# x-Diodes_on_Back_Side.net
KiCad netlist of a schematic drawn in Altium Designer
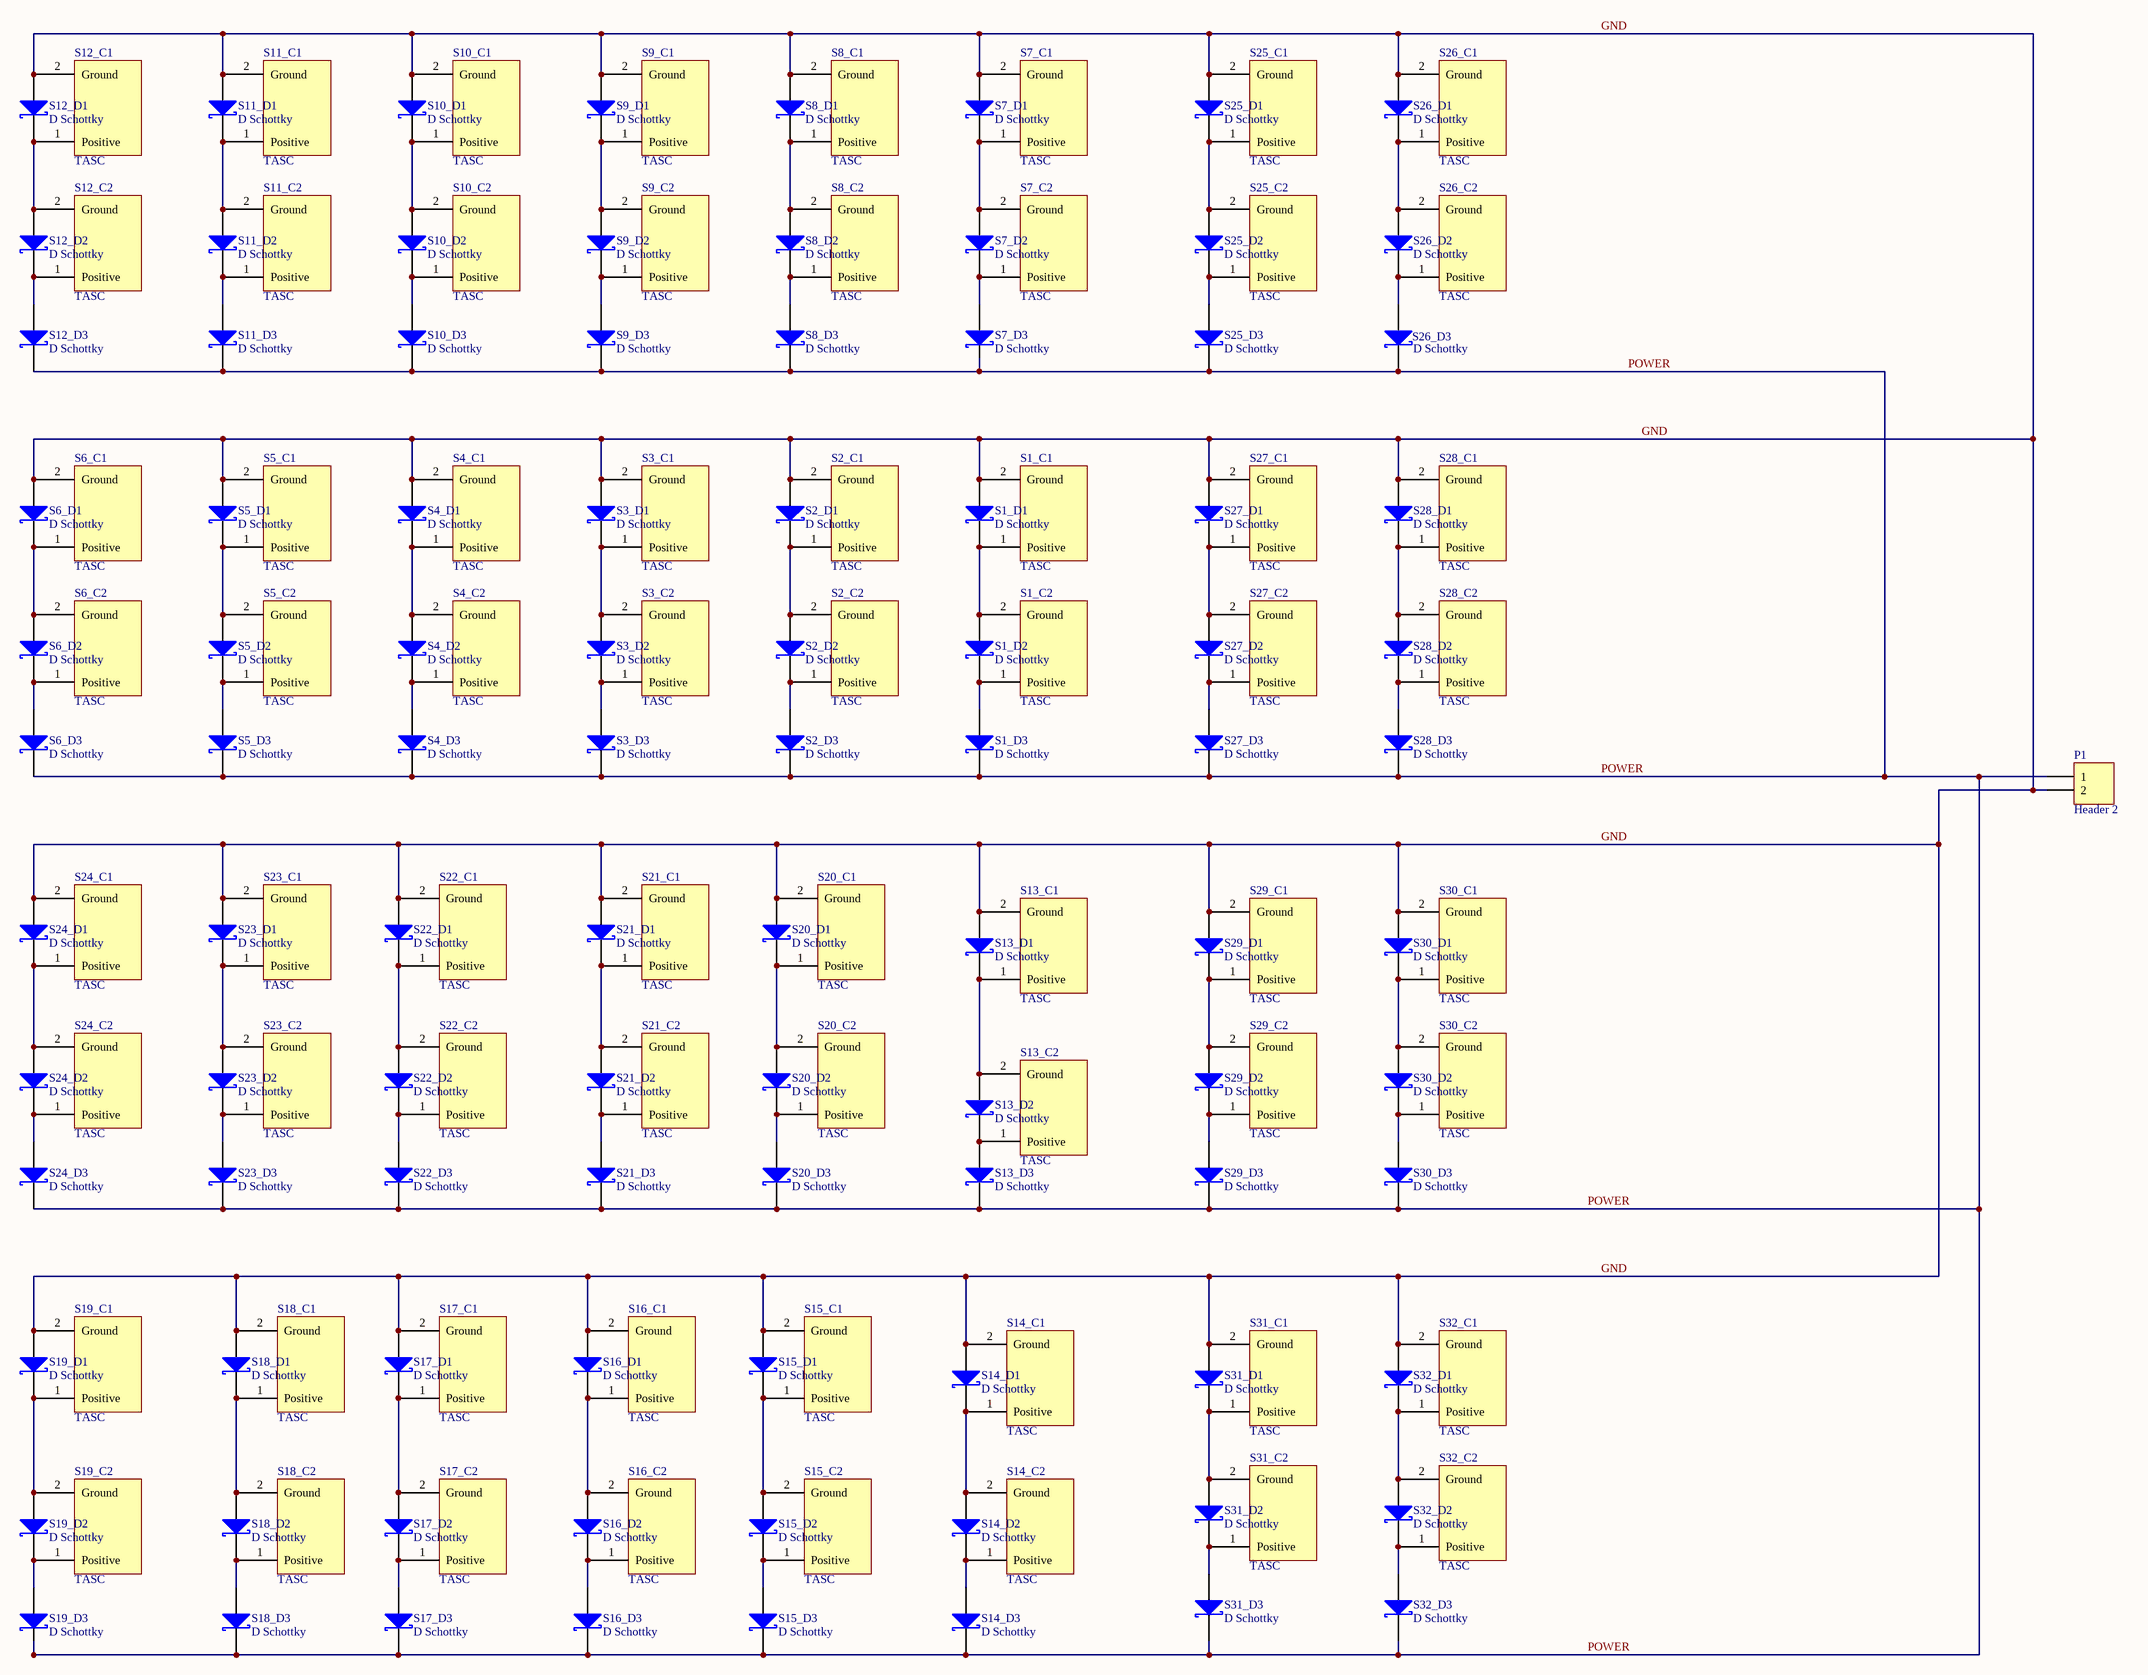
[diagram p0: x-Diodes on Back Side.SchDoc]

(export (version "E")
  (design (tool "Eeschema 10.0.6"))
  (components
    (comp (ref "P1")
      (value "Header 2")
      (footprint "HDR1X2")
      (description "Header, 2-Pin")
      (fields (field (name "PUBLISHER") "Altium Limited"))
      (libsource (lib "Miscellaneous Connectors") (part "Header 2"))
    )
    (comp (ref "S1_C1")
      (value "TASC")
      (footprint "PCBComponent_1")
      (description "TASC Solar Cell")
      (libsource (lib "SolarPanel1") (part "TASC"))
    )
    (comp (ref "S1_C2")
      (value "TASC")
      (footprint "PCBComponent_1")
      (description "TASC Solar Cell")
      (libsource (lib "SolarPanel1") (part "TASC"))
    )
    (comp (ref "S1_D1")
      (value "D Schottky")
      (footprint "SMB")
      (description "Schottky Diode")
      (fields (field (name "PUBLISHER") "Altium Limited"))
      (libsource (lib "Miscellaneous Devices") (part "D Schottky"))
    )
    (comp (ref "S1_D2")
      (value "D Schottky")
      (footprint "SMB")
      (description "Schottky Diode")
      (fields (field (name "PUBLISHER") "Altium Limited"))
      (libsource (lib "Miscellaneous Devices") (part "D Schottky"))
    )
    (comp (ref "S1_D3")
      (value "D Schottky")
      (footprint "SMB")
      (description "Schottky Diode")
      (fields (field (name "PUBLISHER") "Altium Limited"))
      (libsource (lib "Miscellaneous Devices") (part "D Schottky"))
    )
    (comp (ref "S2_C1")
      (value "TASC")
      (footprint "PCBComponent_1")
      (description "TASC Solar Cell")
      (libsource (lib "SolarPanel1") (part "TASC"))
    )
    (comp (ref "S2_C2")
      (value "TASC")
      (footprint "PCBComponent_1")
      (description "TASC Solar Cell")
      (libsource (lib "SolarPanel1") (part "TASC"))
    )
    (comp (ref "S2_D1")
      (value "D Schottky")
      (footprint "SMB")
      (description "Schottky Diode")
      (fields (field (name "PUBLISHER") "Altium Limited"))
      (libsource (lib "Miscellaneous Devices") (part "D Schottky"))
    )
    (comp (ref "S2_D2")
      (value "D Schottky")
      (footprint "SMB")
      (description "Schottky Diode")
      (fields (field (name "PUBLISHER") "Altium Limited"))
      (libsource (lib "Miscellaneous Devices") (part "D Schottky"))
    )
    (comp (ref "S2_D3")
      (value "D Schottky")
      (footprint "SMB")
      (description "Schottky Diode")
      (fields (field (name "PUBLISHER") "Altium Limited"))
      (libsource (lib "Miscellaneous Devices") (part "D Schottky"))
    )
    (comp (ref "S3_C1")
      (value "TASC")
      (footprint "PCBComponent_1")
      (description "TASC Solar Cell")
      (libsource (lib "SolarPanel1") (part "TASC"))
    )
    (comp (ref "S3_C2")
      (value "TASC")
      (footprint "PCBComponent_1")
      (description "TASC Solar Cell")
      (libsource (lib "SolarPanel1") (part "TASC"))
    )
    (comp (ref "S3_D1")
      (value "D Schottky")
      (footprint "SMB")
      (description "Schottky Diode")
      (fields (field (name "PUBLISHER") "Altium Limited"))
      (libsource (lib "Miscellaneous Devices") (part "D Schottky"))
    )
    (comp (ref "S3_D2")
      (value "D Schottky")
      (footprint "SMB")
      (description "Schottky Diode")
      (fields (field (name "PUBLISHER") "Altium Limited"))
      (libsource (lib "Miscellaneous Devices") (part "D Schottky"))
    )
    (comp (ref "S3_D3")
      (value "D Schottky")
      (footprint "SMB")
      (description "Schottky Diode")
      (fields (field (name "PUBLISHER") "Altium Limited"))
      (libsource (lib "Miscellaneous Devices") (part "D Schottky"))
    )
    (comp (ref "S4_C1")
      (value "TASC")
      (footprint "PCBComponent_1")
      (description "TASC Solar Cell")
      (libsource (lib "SolarPanel1") (part "TASC"))
    )
    (comp (ref "S4_C2")
      (value "TASC")
      (footprint "PCBComponent_1")
      (description "TASC Solar Cell")
      (libsource (lib "SolarPanel1") (part "TASC"))
    )
    (comp (ref "S4_D1")
      (value "D Schottky")
      (footprint "SMB")
      (description "Schottky Diode")
      (fields (field (name "PUBLISHER") "Altium Limited"))
      (libsource (lib "Miscellaneous Devices") (part "D Schottky"))
    )
    (comp (ref "S4_D2")
      (value "D Schottky")
      (footprint "SMB")
      (description "Schottky Diode")
      (fields (field (name "PUBLISHER") "Altium Limited"))
      (libsource (lib "Miscellaneous Devices") (part "D Schottky"))
    )
    (comp (ref "S4_D3")
      (value "D Schottky")
      (footprint "SMB")
      (description "Schottky Diode")
      (fields (field (name "PUBLISHER") "Altium Limited"))
      (libsource (lib "Miscellaneous Devices") (part "D Schottky"))
    )
    (comp (ref "S5_C1")
      (value "TASC")
      (footprint "PCBComponent_1")
      (description "TASC Solar Cell")
      (libsource (lib "SolarPanel1") (part "TASC"))
    )
    (comp (ref "S5_C2")
      (value "TASC")
      (footprint "PCBComponent_1")
      (description "TASC Solar Cell")
      (libsource (lib "SolarPanel1") (part "TASC"))
    )
    (comp (ref "S5_D1")
      (value "D Schottky")
      (footprint "SMB")
      (description "Schottky Diode")
      (fields (field (name "PUBLISHER") "Altium Limited"))
      (libsource (lib "Miscellaneous Devices") (part "D Schottky"))
    )
    (comp (ref "S5_D2")
      (value "D Schottky")
      (footprint "SMB")
      (description "Schottky Diode")
      (fields (field (name "PUBLISHER") "Altium Limited"))
      (libsource (lib "Miscellaneous Devices") (part "D Schottky"))
    )
    (comp (ref "S5_D3")
      (value "D Schottky")
      (footprint "SMB")
      (description "Schottky Diode")
      (fields (field (name "PUBLISHER") "Altium Limited"))
      (libsource (lib "Miscellaneous Devices") (part "D Schottky"))
    )
    (comp (ref "S6_C1")
      (value "TASC")
      (footprint "PCBComponent_1")
      (description "TASC Solar Cell")
      (libsource (lib "SolarPanel1") (part "TASC"))
    )
    (comp (ref "S6_C2")
      (value "TASC")
      (footprint "PCBComponent_1")
      (description "TASC Solar Cell")
      (libsource (lib "SolarPanel1") (part "TASC"))
    )
    (comp (ref "S6_D1")
      (value "D Schottky")
      (footprint "SMB")
      (description "Schottky Diode")
      (fields (field (name "PUBLISHER") "Altium Limited"))
      (libsource (lib "Miscellaneous Devices") (part "D Schottky"))
    )
    (comp (ref "S6_D2")
      (value "D Schottky")
      (footprint "SMB")
      (description "Schottky Diode")
      (fields (field (name "PUBLISHER") "Altium Limited"))
      (libsource (lib "Miscellaneous Devices") (part "D Schottky"))
    )
    (comp (ref "S6_D3")
      (value "D Schottky")
      (footprint "SMB")
      (description "Schottky Diode")
      (fields (field (name "PUBLISHER") "Altium Limited"))
      (libsource (lib "Miscellaneous Devices") (part "D Schottky"))
    )
    (comp (ref "S7_C1")
      (value "TASC")
      (footprint "PCBComponent_1")
      (description "TASC Solar Cell")
      (libsource (lib "SolarPanel1") (part "TASC"))
    )
    (comp (ref "S7_C2")
      (value "TASC")
      (footprint "PCBComponent_1")
      (description "TASC Solar Cell")
      (libsource (lib "SolarPanel1") (part "TASC"))
    )
    (comp (ref "S7_D1")
      (value "D Schottky")
      (footprint "SMB")
      (description "Schottky Diode")
      (fields (field (name "PUBLISHER") "Altium Limited"))
      (libsource (lib "Miscellaneous Devices") (part "D Schottky"))
    )
    (comp (ref "S7_D2")
      (value "D Schottky")
      (footprint "SMB")
      (description "Schottky Diode")
      (fields (field (name "PUBLISHER") "Altium Limited"))
      (libsource (lib "Miscellaneous Devices") (part "D Schottky"))
    )
    (comp (ref "S7_D3")
      (value "D Schottky")
      (footprint "SMB")
      (description "Schottky Diode")
      (fields (field (name "PUBLISHER") "Altium Limited"))
      (libsource (lib "Miscellaneous Devices") (part "D Schottky"))
    )
    (comp (ref "S8_C1")
      (value "TASC")
      (footprint "PCBComponent_1")
      (description "TASC Solar Cell")
      (libsource (lib "SolarPanel1") (part "TASC"))
    )
    (comp (ref "S8_C2")
      (value "TASC")
      (footprint "PCBComponent_1")
      (description "TASC Solar Cell")
      (libsource (lib "SolarPanel1") (part "TASC"))
    )
    (comp (ref "S8_D1")
      (value "D Schottky")
      (footprint "SMB")
      (description "Schottky Diode")
      (fields (field (name "PUBLISHER") "Altium Limited"))
      (libsource (lib "Miscellaneous Devices") (part "D Schottky"))
    )
    (comp (ref "S8_D2")
      (value "D Schottky")
      (footprint "SMB")
      (description "Schottky Diode")
      (fields (field (name "PUBLISHER") "Altium Limited"))
      (libsource (lib "Miscellaneous Devices") (part "D Schottky"))
    )
    (comp (ref "S8_D3")
      (value "D Schottky")
      (footprint "SMB")
      (description "Schottky Diode")
      (fields (field (name "PUBLISHER") "Altium Limited"))
      (libsource (lib "Miscellaneous Devices") (part "D Schottky"))
    )
    (comp (ref "S9_C1")
      (value "TASC")
      (footprint "PCBComponent_1")
      (description "TASC Solar Cell")
      (libsource (lib "SolarPanel1") (part "TASC"))
    )
    (comp (ref "S9_C2")
      (value "TASC")
      (footprint "PCBComponent_1")
      (description "TASC Solar Cell")
      (libsource (lib "SolarPanel1") (part "TASC"))
    )
    (comp (ref "S9_D1")
      (value "D Schottky")
      (footprint "SMB")
      (description "Schottky Diode")
      (fields (field (name "PUBLISHER") "Altium Limited"))
      (libsource (lib "Miscellaneous Devices") (part "D Schottky"))
    )
    (comp (ref "S9_D2")
      (value "D Schottky")
      (footprint "SMB")
      (description "Schottky Diode")
      (fields (field (name "PUBLISHER") "Altium Limited"))
      (libsource (lib "Miscellaneous Devices") (part "D Schottky"))
    )
    (comp (ref "S9_D3")
      (value "D Schottky")
      (footprint "SMB")
      (description "Schottky Diode")
      (fields (field (name "PUBLISHER") "Altium Limited"))
      (libsource (lib "Miscellaneous Devices") (part "D Schottky"))
    )
    (comp (ref "S10_C1")
      (value "TASC")
      (footprint "PCBComponent_1")
      (description "TASC Solar Cell")
      (libsource (lib "SolarPanel1") (part "TASC"))
    )
    (comp (ref "S10_C2")
      (value "TASC")
      (footprint "PCBComponent_1")
      (description "TASC Solar Cell")
      (libsource (lib "SolarPanel1") (part "TASC"))
    )
    (comp (ref "S10_D1")
      (value "D Schottky")
      (footprint "SMB")
      (description "Schottky Diode")
      (fields (field (name "PUBLISHER") "Altium Limited"))
      (libsource (lib "Miscellaneous Devices") (part "D Schottky"))
    )
    (comp (ref "S10_D2")
      (value "D Schottky")
      (footprint "SMB")
      (description "Schottky Diode")
      (fields (field (name "PUBLISHER") "Altium Limited"))
      (libsource (lib "Miscellaneous Devices") (part "D Schottky"))
    )
    (comp (ref "S10_D3")
      (value "D Schottky")
      (footprint "SMB")
      (description "Schottky Diode")
      (fields (field (name "PUBLISHER") "Altium Limited"))
      (libsource (lib "Miscellaneous Devices") (part "D Schottky"))
    )
    (comp (ref "S11_C1")
      (value "TASC")
      (footprint "PCBComponent_1")
      (description "TASC Solar Cell")
      (libsource (lib "SolarPanel1") (part "TASC"))
    )
    (comp (ref "S11_C2")
      (value "TASC")
      (footprint "PCBComponent_1")
      (description "TASC Solar Cell")
      (libsource (lib "SolarPanel1") (part "TASC"))
    )
    (comp (ref "S11_D1")
      (value "D Schottky")
      (footprint "SMB")
      (description "Schottky Diode")
      (fields (field (name "PUBLISHER") "Altium Limited"))
      (libsource (lib "Miscellaneous Devices") (part "D Schottky"))
    )
    (comp (ref "S11_D2")
      (value "D Schottky")
      (footprint "SMB")
      (description "Schottky Diode")
      (fields (field (name "PUBLISHER") "Altium Limited"))
      (libsource (lib "Miscellaneous Devices") (part "D Schottky"))
    )
    (comp (ref "S11_D3")
      (value "D Schottky")
      (footprint "SMB")
      (description "Schottky Diode")
      (fields (field (name "PUBLISHER") "Altium Limited"))
      (libsource (lib "Miscellaneous Devices") (part "D Schottky"))
    )
    (comp (ref "S12_C1")
      (value "TASC")
      (footprint "PCBComponent_1")
      (description "TASC Solar Cell")
      (libsource (lib "SolarPanel1") (part "TASC"))
    )
    (comp (ref "S12_C2")
      (value "TASC")
      (footprint "PCBComponent_1")
      (description "TASC Solar Cell")
      (libsource (lib "SolarPanel1") (part "TASC"))
    )
    (comp (ref "S12_D1")
      (value "D Schottky")
      (footprint "SMB")
      (description "Schottky Diode")
      (fields (field (name "PUBLISHER") "Altium Limited"))
      (libsource (lib "Miscellaneous Devices") (part "D Schottky"))
    )
    (comp (ref "S12_D2")
      (value "D Schottky")
      (footprint "SMB")
      (description "Schottky Diode")
      (fields (field (name "PUBLISHER") "Altium Limited"))
      (libsource (lib "Miscellaneous Devices") (part "D Schottky"))
    )
    (comp (ref "S12_D3")
      (value "D Schottky")
      (footprint "SMB")
      (description "Schottky Diode")
      (fields (field (name "PUBLISHER") "Altium Limited"))
      (libsource (lib "Miscellaneous Devices") (part "D Schottky"))
    )
    (comp (ref "S13_C1")
      (value "TASC")
      (footprint "PCBComponent_1")
      (description "TASC Solar Cell")
      (libsource (lib "SolarPanel1") (part "TASC"))
    )
    (comp (ref "S13_C2")
      (value "TASC")
      (footprint "PCBComponent_1")
      (description "TASC Solar Cell")
      (libsource (lib "SolarPanel1") (part "TASC"))
    )
    (comp (ref "S13_D1")
      (value "D Schottky")
      (footprint "SMB")
      (description "Schottky Diode")
      (fields (field (name "PUBLISHER") "Altium Limited"))
      (libsource (lib "Miscellaneous Devices") (part "D Schottky"))
    )
    (comp (ref "S13_D2")
      (value "D Schottky")
      (footprint "SMB")
      (description "Schottky Diode")
      (fields (field (name "PUBLISHER") "Altium Limited"))
      (libsource (lib "Miscellaneous Devices") (part "D Schottky"))
    )
    (comp (ref "S13_D3")
      (value "D Schottky")
      (footprint "SMB")
      (description "Schottky Diode")
      (fields (field (name "PUBLISHER") "Altium Limited"))
      (libsource (lib "Miscellaneous Devices") (part "D Schottky"))
    )
    (comp (ref "S14_C1")
      (value "TASC")
      (footprint "PCBComponent_1")
      (description "TASC Solar Cell")
      (libsource (lib "SolarPanel1") (part "TASC"))
    )
    (comp (ref "S14_C2")
      (value "TASC")
      (footprint "PCBComponent_1")
      (description "TASC Solar Cell")
      (libsource (lib "SolarPanel1") (part "TASC"))
    )
    (comp (ref "S14_D1")
      (value "D Schottky")
      (footprint "SMB")
      (description "Schottky Diode")
      (fields (field (name "PUBLISHER") "Altium Limited"))
      (libsource (lib "Miscellaneous Devices") (part "D Schottky"))
    )
    (comp (ref "S14_D2")
      (value "D Schottky")
      (footprint "SMB")
      (description "Schottky Diode")
      (fields (field (name "PUBLISHER") "Altium Limited"))
      (libsource (lib "Miscellaneous Devices") (part "D Schottky"))
    )
    (comp (ref "S14_D3")
      (value "D Schottky")
      (footprint "SMB")
      (description "Schottky Diode")
      (fields (field (name "PUBLISHER") "Altium Limited"))
      (libsource (lib "Miscellaneous Devices") (part "D Schottky"))
    )
    (comp (ref "S15_C1")
      (value "TASC")
      (footprint "PCBComponent_1")
      (description "TASC Solar Cell")
      (libsource (lib "SolarPanel1") (part "TASC"))
    )
    (comp (ref "S15_C2")
      (value "TASC")
      (footprint "PCBComponent_1")
      (description "TASC Solar Cell")
      (libsource (lib "SolarPanel1") (part "TASC"))
    )
    (comp (ref "S15_D1")
      (value "D Schottky")
      (footprint "SMB")
      (description "Schottky Diode")
      (fields (field (name "PUBLISHER") "Altium Limited"))
      (libsource (lib "Miscellaneous Devices") (part "D Schottky"))
    )
    (comp (ref "S15_D2")
      (value "D Schottky")
      (footprint "SMB")
      (description "Schottky Diode")
      (fields (field (name "PUBLISHER") "Altium Limited"))
      (libsource (lib "Miscellaneous Devices") (part "D Schottky"))
    )
    (comp (ref "S15_D3")
      (value "D Schottky")
      (footprint "SMB")
      (description "Schottky Diode")
      (fields (field (name "PUBLISHER") "Altium Limited"))
      (libsource (lib "Miscellaneous Devices") (part "D Schottky"))
    )
    (comp (ref "S16_C1")
      (value "TASC")
      (footprint "PCBComponent_1")
      (description "TASC Solar Cell")
      (libsource (lib "SolarPanel1") (part "TASC"))
    )
    (comp (ref "S16_C2")
      (value "TASC")
      (footprint "PCBComponent_1")
      (description "TASC Solar Cell")
      (libsource (lib "SolarPanel1") (part "TASC"))
    )
    (comp (ref "S16_D1")
      (value "D Schottky")
      (footprint "SMB")
      (description "Schottky Diode")
      (fields (field (name "PUBLISHER") "Altium Limited"))
      (libsource (lib "Miscellaneous Devices") (part "D Schottky"))
    )
    (comp (ref "S16_D2")
      (value "D Schottky")
      (footprint "SMB")
      (description "Schottky Diode")
      (fields (field (name "PUBLISHER") "Altium Limited"))
      (libsource (lib "Miscellaneous Devices") (part "D Schottky"))
    )
    (comp (ref "S16_D3")
      (value "D Schottky")
      (footprint "SMB")
      (description "Schottky Diode")
      (fields (field (name "PUBLISHER") "Altium Limited"))
      (libsource (lib "Miscellaneous Devices") (part "D Schottky"))
    )
    (comp (ref "S17_C1")
      (value "TASC")
      (footprint "PCBComponent_1")
      (description "TASC Solar Cell")
      (libsource (lib "SolarPanel1") (part "TASC"))
    )
    (comp (ref "S17_C2")
      (value "TASC")
      (footprint "PCBComponent_1")
      (description "TASC Solar Cell")
      (libsource (lib "SolarPanel1") (part "TASC"))
    )
    (comp (ref "S17_D1")
      (value "D Schottky")
      (footprint "SMB")
      (description "Schottky Diode")
      (fields (field (name "PUBLISHER") "Altium Limited"))
      (libsource (lib "Miscellaneous Devices") (part "D Schottky"))
    )
    (comp (ref "S17_D2")
      (value "D Schottky")
      (footprint "SMB")
      (description "Schottky Diode")
      (fields (field (name "PUBLISHER") "Altium Limited"))
      (libsource (lib "Miscellaneous Devices") (part "D Schottky"))
    )
    (comp (ref "S17_D3")
      (value "D Schottky")
      (footprint "SMB")
      (description "Schottky Diode")
      (fields (field (name "PUBLISHER") "Altium Limited"))
      (libsource (lib "Miscellaneous Devices") (part "D Schottky"))
    )
    (comp (ref "S18_C1")
      (value "TASC")
      (footprint "PCBComponent_1")
      (description "TASC Solar Cell")
      (libsource (lib "SolarPanel1") (part "TASC"))
    )
    (comp (ref "S18_C2")
      (value "TASC")
      (footprint "PCBComponent_1")
      (description "TASC Solar Cell")
      (libsource (lib "SolarPanel1") (part "TASC"))
    )
    (comp (ref "S18_D1")
      (value "D Schottky")
      (footprint "SMB")
      (description "Schottky Diode")
      (fields (field (name "PUBLISHER") "Altium Limited"))
      (libsource (lib "Miscellaneous Devices") (part "D Schottky"))
    )
    (comp (ref "S18_D2")
      (value "D Schottky")
      (footprint "SMB")
      (description "Schottky Diode")
      (fields (field (name "PUBLISHER") "Altium Limited"))
      (libsource (lib "Miscellaneous Devices") (part "D Schottky"))
    )
    (comp (ref "S18_D3")
      (value "D Schottky")
      (footprint "SMB")
      (description "Schottky Diode")
      (fields (field (name "PUBLISHER") "Altium Limited"))
      (libsource (lib "Miscellaneous Devices") (part "D Schottky"))
    )
    (comp (ref "S19_C1")
      (value "TASC")
      (footprint "PCBComponent_1")
      (description "TASC Solar Cell")
      (libsource (lib "SolarPanel1") (part "TASC"))
    )
    (comp (ref "S19_C2")
      (value "TASC")
      (footprint "PCBComponent_1")
      (description "TASC Solar Cell")
      (libsource (lib "SolarPanel1") (part "TASC"))
    )
    (comp (ref "S19_D1")
      (value "D Schottky")
      (footprint "SMB")
      (description "Schottky Diode")
      (fields (field (name "PUBLISHER") "Altium Limited"))
      (libsource (lib "Miscellaneous Devices") (part "D Schottky"))
    )
    (comp (ref "S19_D2")
      (value "D Schottky")
      (footprint "SMB")
      (description "Schottky Diode")
      (fields (field (name "PUBLISHER") "Altium Limited"))
      (libsource (lib "Miscellaneous Devices") (part "D Schottky"))
    )
    (comp (ref "S19_D3")
      (value "D Schottky")
      (footprint "SMB")
      (description "Schottky Diode")
      (fields (field (name "PUBLISHER") "Altium Limited"))
      (libsource (lib "Miscellaneous Devices") (part "D Schottky"))
    )
    (comp (ref "S20_C1")
      (value "TASC")
      (footprint "PCBComponent_1")
      (description "TASC Solar Cell")
      (libsource (lib "SolarPanel1") (part "TASC"))
    )
    (comp (ref "S20_C2")
      (value "TASC")
      (footprint "PCBComponent_1")
      (description "TASC Solar Cell")
      (libsource (lib "SolarPanel1") (part "TASC"))
    )
    (comp (ref "S20_D1")
      (value "D Schottky")
      (footprint "SMB")
      (description "Schottky Diode")
      (fields (field (name "PUBLISHER") "Altium Limited"))
      (libsource (lib "Miscellaneous Devices") (part "D Schottky"))
    )
    (comp (ref "S20_D2")
      (value "D Schottky")
      (footprint "SMB")
      (description "Schottky Diode")
      (fields (field (name "PUBLISHER") "Altium Limited"))
      (libsource (lib "Miscellaneous Devices") (part "D Schottky"))
    )
    (comp (ref "S20_D3")
      (value "D Schottky")
      (footprint "SMB")
      (description "Schottky Diode")
      (fields (field (name "PUBLISHER") "Altium Limited"))
      (libsource (lib "Miscellaneous Devices") (part "D Schottky"))
    )
    (comp (ref "S21_C1")
      (value "TASC")
      (footprint "PCBComponent_1")
      (description "TASC Solar Cell")
      (libsource (lib "SolarPanel1") (part "TASC"))
    )
    (comp (ref "S21_C2")
      (value "TASC")
      (footprint "PCBComponent_1")
      (description "TASC Solar Cell")
      (libsource (lib "SolarPanel1") (part "TASC"))
    )
    (comp (ref "S21_D1")
      (value "D Schottky")
      (footprint "SMB")
      (description "Schottky Diode")
      (fields (field (name "PUBLISHER") "Altium Limited"))
      (libsource (lib "Miscellaneous Devices") (part "D Schottky"))
    )
    (comp (ref "S21_D2")
      (value "D Schottky")
      (footprint "SMB")
      (description "Schottky Diode")
      (fields (field (name "PUBLISHER") "Altium Limited"))
      (libsource (lib "Miscellaneous Devices") (part "D Schottky"))
    )
    (comp (ref "S21_D3")
      (value "D Schottky")
      (footprint "SMB")
      (description "Schottky Diode")
      (fields (field (name "PUBLISHER") "Altium Limited"))
      (libsource (lib "Miscellaneous Devices") (part "D Schottky"))
    )
    (comp (ref "S22_C1")
      (value "TASC")
      (footprint "PCBComponent_1")
      (description "TASC Solar Cell")
      (libsource (lib "SolarPanel1") (part "TASC"))
    )
    (comp (ref "S22_C2")
      (value "TASC")
      (footprint "PCBComponent_1")
      (description "TASC Solar Cell")
      (libsource (lib "SolarPanel1") (part "TASC"))
    )
    (comp (ref "S22_D1")
      (value "D Schottky")
      (footprint "SMB")
      (description "Schottky Diode")
      (fields (field (name "PUBLISHER") "Altium Limited"))
      (libsource (lib "Miscellaneous Devices") (part "D Schottky"))
    )
    (comp (ref "S22_D2")
      (value "D Schottky")
      (footprint "SMB")
      (description "Schottky Diode")
      (fields (field (name "PUBLISHER") "Altium Limited"))
      (libsource (lib "Miscellaneous Devices") (part "D Schottky"))
    )
    (comp (ref "S22_D3")
      (value "D Schottky")
      (footprint "SMB")
      (description "Schottky Diode")
      (fields (field (name "PUBLISHER") "Altium Limited"))
      (libsource (lib "Miscellaneous Devices") (part "D Schottky"))
    )
    (comp (ref "S23_C1")
      (value "TASC")
      (footprint "PCBComponent_1")
      (description "TASC Solar Cell")
      (libsource (lib "SolarPanel1") (part "TASC"))
    )
    (comp (ref "S23_C2")
      (value "TASC")
      (footprint "PCBComponent_1")
      (description "TASC Solar Cell")
      (libsource (lib "SolarPanel1") (part "TASC"))
    )
    (comp (ref "S23_D1")
      (value "D Schottky")
      (footprint "SMB")
      (description "Schottky Diode")
      (fields (field (name "PUBLISHER") "Altium Limited"))
      (libsource (lib "Miscellaneous Devices") (part "D Schottky"))
    )
    (comp (ref "S23_D2")
      (value "D Schottky")
      (footprint "SMB")
      (description "Schottky Diode")
      (fields (field (name "PUBLISHER") "Altium Limited"))
      (libsource (lib "Miscellaneous Devices") (part "D Schottky"))
    )
    (comp (ref "S23_D3")
      (value "D Schottky")
      (footprint "SMB")
      (description "Schottky Diode")
      (fields (field (name "PUBLISHER") "Altium Limited"))
      (libsource (lib "Miscellaneous Devices") (part "D Schottky"))
    )
    (comp (ref "S24_C1")
      (value "TASC")
      (footprint "PCBComponent_1")
      (description "TASC Solar Cell")
      (libsource (lib "SolarPanel1") (part "TASC"))
    )
    (comp (ref "S24_C2")
      (value "TASC")
      (footprint "PCBComponent_1")
      (description "TASC Solar Cell")
      (libsource (lib "SolarPanel1") (part "TASC"))
    )
    (comp (ref "S24_D1")
      (value "D Schottky")
      (footprint "SMB")
      (description "Schottky Diode")
      (fields (field (name "PUBLISHER") "Altium Limited"))
      (libsource (lib "Miscellaneous Devices") (part "D Schottky"))
    )
    (comp (ref "S24_D2")
      (value "D Schottky")
      (footprint "SMB")
      (description "Schottky Diode")
      (fields (field (name "PUBLISHER") "Altium Limited"))
      (libsource (lib "Miscellaneous Devices") (part "D Schottky"))
    )
    (comp (ref "S24_D3")
      (value "D Schottky")
      (footprint "SMB")
      (description "Schottky Diode")
      (fields (field (name "PUBLISHER") "Altium Limited"))
      (libsource (lib "Miscellaneous Devices") (part "D Schottky"))
    )
    (comp (ref "S25_C1")
      (value "TASC")
      (footprint "PCBComponent_1")
      (description "TASC Solar Cell")
      (libsource (lib "SolarPanel1") (part "TASC"))
    )
    (comp (ref "S25_C2")
      (value "TASC")
      (footprint "PCBComponent_1")
      (description "TASC Solar Cell")
      (libsource (lib "SolarPanel1") (part "TASC"))
    )
    (comp (ref "S25_D1")
      (value "D Schottky")
      (footprint "SMB")
      (description "Schottky Diode")
      (fields (field (name "PUBLISHER") "Altium Limited"))
      (libsource (lib "Miscellaneous Devices") (part "D Schottky"))
    )
    (comp (ref "S25_D2")
      (value "D Schottky")
      (footprint "SMB")
      (description "Schottky Diode")
      (fields (field (name "PUBLISHER") "Altium Limited"))
      (libsource (lib "Miscellaneous Devices") (part "D Schottky"))
    )
    (comp (ref "S25_D3")
      (value "D Schottky")
      (footprint "SMB")
      (description "Schottky Diode")
      (fields (field (name "PUBLISHER") "Altium Limited"))
      (libsource (lib "Miscellaneous Devices") (part "D Schottky"))
    )
    (comp (ref "S26_C1")
      (value "TASC")
      (footprint "PCBComponent_1")
      (description "TASC Solar Cell")
      (libsource (lib "SolarPanel1") (part "TASC"))
    )
    (comp (ref "S26_C2")
      (value "TASC")
      (footprint "PCBComponent_1")
      (description "TASC Solar Cell")
      (libsource (lib "SolarPanel1") (part "TASC"))
    )
    (comp (ref "S26_D1")
      (value "D Schottky")
      (footprint "SMB")
      (description "Schottky Diode")
      (fields (field (name "PUBLISHER") "Altium Limited"))
      (libsource (lib "Miscellaneous Devices") (part "D Schottky"))
    )
    (comp (ref "S26_D2")
      (value "D Schottky")
      (footprint "SMB")
      (description "Schottky Diode")
      (fields (field (name "PUBLISHER") "Altium Limited"))
      (libsource (lib "Miscellaneous Devices") (part "D Schottky"))
    )
    (comp (ref "S26_D3")
      (value "D Schottky")
      (footprint "SMB")
      (description "Schottky Diode")
      (fields (field (name "PUBLISHER") "Altium Limited"))
      (libsource (lib "Miscellaneous Devices") (part "D Schottky"))
    )
    (comp (ref "S27_C1")
      (value "TASC")
      (footprint "PCBComponent_1")
      (description "TASC Solar Cell")
      (libsource (lib "SolarPanel1") (part "TASC"))
    )
    (comp (ref "S27_C2")
      (value "TASC")
      (footprint "PCBComponent_1")
      (description "TASC Solar Cell")
      (libsource (lib "SolarPanel1") (part "TASC"))
    )
    (comp (ref "S27_D1")
      (value "D Schottky")
      (footprint "SMB")
      (description "Schottky Diode")
      (fields (field (name "PUBLISHER") "Altium Limited"))
      (libsource (lib "Miscellaneous Devices") (part "D Schottky"))
    )
    (comp (ref "S27_D2")
      (value "D Schottky")
      (footprint "SMB")
      (description "Schottky Diode")
      (fields (field (name "PUBLISHER") "Altium Limited"))
      (libsource (lib "Miscellaneous Devices") (part "D Schottky"))
    )
    (comp (ref "S27_D3")
      (value "D Schottky")
      (footprint "SMB")
      (description "Schottky Diode")
      (fields (field (name "PUBLISHER") "Altium Limited"))
      (libsource (lib "Miscellaneous Devices") (part "D Schottky"))
    )
    (comp (ref "S28_C1")
      (value "TASC")
      (footprint "PCBComponent_1")
      (description "TASC Solar Cell")
      (libsource (lib "SolarPanel1") (part "TASC"))
    )
    (comp (ref "S28_C2")
      (value "TASC")
      (footprint "PCBComponent_1")
      (description "TASC Solar Cell")
      (libsource (lib "SolarPanel1") (part "TASC"))
    )
    (comp (ref "S28_D1")
      (value "D Schottky")
      (footprint "SMB")
      (description "Schottky Diode")
      (fields (field (name "PUBLISHER") "Altium Limited"))
      (libsource (lib "Miscellaneous Devices") (part "D Schottky"))
    )
    (comp (ref "S28_D2")
      (value "D Schottky")
      (footprint "SMB")
      (description "Schottky Diode")
      (fields (field (name "PUBLISHER") "Altium Limited"))
      (libsource (lib "Miscellaneous Devices") (part "D Schottky"))
    )
    (comp (ref "S28_D3")
      (value "D Schottky")
      (footprint "SMB")
      (description "Schottky Diode")
      (fields (field (name "PUBLISHER") "Altium Limited"))
      (libsource (lib "Miscellaneous Devices") (part "D Schottky"))
    )
    (comp (ref "S29_C1")
      (value "TASC")
      (footprint "PCBComponent_1")
      (description "TASC Solar Cell")
      (libsource (lib "SolarPanel1") (part "TASC"))
    )
    (comp (ref "S29_C2")
      (value "TASC")
      (footprint "PCBComponent_1")
      (description "TASC Solar Cell")
      (libsource (lib "SolarPanel1") (part "TASC"))
    )
    (comp (ref "S29_D1")
      (value "D Schottky")
      (footprint "SMB")
      (description "Schottky Diode")
      (fields (field (name "PUBLISHER") "Altium Limited"))
      (libsource (lib "Miscellaneous Devices") (part "D Schottky"))
    )
    (comp (ref "S29_D2")
      (value "D Schottky")
      (footprint "SMB")
      (description "Schottky Diode")
      (fields (field (name "PUBLISHER") "Altium Limited"))
      (libsource (lib "Miscellaneous Devices") (part "D Schottky"))
    )
    (comp (ref "S29_D3")
      (value "D Schottky")
      (footprint "SMB")
      (description "Schottky Diode")
      (fields (field (name "PUBLISHER") "Altium Limited"))
      (libsource (lib "Miscellaneous Devices") (part "D Schottky"))
    )
    (comp (ref "S30_C1")
      (value "TASC")
      (footprint "PCBComponent_1")
      (description "TASC Solar Cell")
      (libsource (lib "SolarPanel1") (part "TASC"))
    )
    (comp (ref "S30_C2")
      (value "TASC")
      (footprint "PCBComponent_1")
      (description "TASC Solar Cell")
      (libsource (lib "SolarPanel1") (part "TASC"))
    )
    (comp (ref "S30_D1")
      (value "D Schottky")
      (footprint "SMB")
      (description "Schottky Diode")
      (fields (field (name "PUBLISHER") "Altium Limited"))
      (libsource (lib "Miscellaneous Devices") (part "D Schottky"))
    )
    (comp (ref "S30_D2")
      (value "D Schottky")
      (footprint "SMB")
      (description "Schottky Diode")
      (fields (field (name "PUBLISHER") "Altium Limited"))
      (libsource (lib "Miscellaneous Devices") (part "D Schottky"))
    )
    (comp (ref "S30_D3")
      (value "D Schottky")
      (footprint "SMB")
      (description "Schottky Diode")
      (fields (field (name "PUBLISHER") "Altium Limited"))
      (libsource (lib "Miscellaneous Devices") (part "D Schottky"))
    )
    (comp (ref "S31_C1")
      (value "TASC")
      (footprint "PCBComponent_1")
      (description "TASC Solar Cell")
      (libsource (lib "SolarPanel1") (part "TASC"))
    )
    (comp (ref "S31_C2")
      (value "TASC")
      (footprint "PCBComponent_1")
      (description "TASC Solar Cell")
      (libsource (lib "SolarPanel1") (part "TASC"))
    )
    (comp (ref "S31_D1")
      (value "D Schottky")
      (footprint "SMB")
      (description "Schottky Diode")
      (fields (field (name "PUBLISHER") "Altium Limited"))
      (libsource (lib "Miscellaneous Devices") (part "D Schottky"))
    )
    (comp (ref "S31_D2")
      (value "D Schottky")
      (footprint "SMB")
      (description "Schottky Diode")
      (fields (field (name "PUBLISHER") "Altium Limited"))
      (libsource (lib "Miscellaneous Devices") (part "D Schottky"))
    )
    (comp (ref "S31_D3")
      (value "D Schottky")
      (footprint "SMB")
      (description "Schottky Diode")
      (fields (field (name "PUBLISHER") "Altium Limited"))
      (libsource (lib "Miscellaneous Devices") (part "D Schottky"))
    )
    (comp (ref "S32_C1")
      (value "TASC")
      (footprint "PCBComponent_1")
      (description "TASC Solar Cell")
      (libsource (lib "SolarPanel1") (part "TASC"))
    )
    (comp (ref "S32_C2")
      (value "TASC")
      (footprint "PCBComponent_1")
      (description "TASC Solar Cell")
      (libsource (lib "SolarPanel1") (part "TASC"))
    )
    (comp (ref "S32_D1")
      (value "D Schottky")
      (footprint "SMB")
      (description "Schottky Diode")
      (fields (field (name "PUBLISHER") "Altium Limited"))
      (libsource (lib "Miscellaneous Devices") (part "D Schottky"))
    )
    (comp (ref "S32_D2")
      (value "D Schottky")
      (footprint "SMB")
      (description "Schottky Diode")
      (fields (field (name "PUBLISHER") "Altium Limited"))
      (libsource (lib "Miscellaneous Devices") (part "D Schottky"))
    )
    (comp (ref "S32_D3")
      (value "D Schottky")
      (footprint "SMB")
      (description "Schottky Diode")
      (fields (field (name "PUBLISHER") "Altium Limited"))
      (libsource (lib "Miscellaneous Devices") (part "D Schottky"))
    )
  )
  (nets
    (net (code "1") (name "/GND") (class "Default")
      (node (ref "P1") (pin "2") (pinfunction "2_2") (pintype "passive"))
      (node (ref "S10_C1") (pin "2") (pinfunction "Ground_2") (pintype "power_in"))
      (node (ref "S10_D1") (pin "1") (pinfunction "A_1") (pintype "passive"))
      (node (ref "S11_C1") (pin "2") (pinfunction "Ground_2") (pintype "power_in"))
      (node (ref "S11_D1") (pin "1") (pinfunction "A_1") (pintype "passive"))
      (node (ref "S12_C1") (pin "2") (pinfunction "Ground_2") (pintype "power_in"))
      (node (ref "S12_D1") (pin "1") (pinfunction "A_1") (pintype "passive"))
      (node (ref "S13_C1") (pin "2") (pinfunction "Ground_2") (pintype "power_in"))
      (node (ref "S13_D1") (pin "1") (pinfunction "A_1") (pintype "passive"))
      (node (ref "S14_C1") (pin "2") (pinfunction "Ground_2") (pintype "power_in"))
      (node (ref "S14_D1") (pin "1") (pinfunction "A_1") (pintype "passive"))
      (node (ref "S15_C1") (pin "2") (pinfunction "Ground_2") (pintype "power_in"))
      (node (ref "S15_D1") (pin "1") (pinfunction "A_1") (pintype "passive"))
      (node (ref "S16_C1") (pin "2") (pinfunction "Ground_2") (pintype "power_in"))
      (node (ref "S16_D1") (pin "1") (pinfunction "A_1") (pintype "passive"))
      (node (ref "S17_C1") (pin "2") (pinfunction "Ground_2") (pintype "power_in"))
      (node (ref "S17_D1") (pin "1") (pinfunction "A_1") (pintype "passive"))
      (node (ref "S18_C1") (pin "2") (pinfunction "Ground_2") (pintype "power_in"))
      (node (ref "S18_D1") (pin "1") (pinfunction "A_1") (pintype "passive"))
      (node (ref "S19_C1") (pin "2") (pinfunction "Ground_2") (pintype "power_in"))
      (node (ref "S19_D1") (pin "1") (pinfunction "A_1") (pintype "passive"))
      (node (ref "S1_C1") (pin "2") (pinfunction "Ground_2") (pintype "power_in"))
      (node (ref "S1_D1") (pin "1") (pinfunction "A_1") (pintype "passive"))
      (node (ref "S20_C1") (pin "2") (pinfunction "Ground_2") (pintype "power_in"))
      (node (ref "S20_D1") (pin "1") (pinfunction "A_1") (pintype "passive"))
      (node (ref "S21_C1") (pin "2") (pinfunction "Ground_2") (pintype "power_in"))
      (node (ref "S21_D1") (pin "1") (pinfunction "A_1") (pintype "passive"))
      (node (ref "S22_C1") (pin "2") (pinfunction "Ground_2") (pintype "power_in"))
      (node (ref "S22_D1") (pin "1") (pinfunction "A_1") (pintype "passive"))
      (node (ref "S23_C1") (pin "2") (pinfunction "Ground_2") (pintype "power_in"))
      (node (ref "S23_D1") (pin "1") (pinfunction "A_1") (pintype "passive"))
      (node (ref "S24_C1") (pin "2") (pinfunction "Ground_2") (pintype "power_in"))
      (node (ref "S24_D1") (pin "1") (pinfunction "A_1") (pintype "passive"))
      (node (ref "S25_C1") (pin "2") (pinfunction "Ground_2") (pintype "power_in"))
      (node (ref "S25_D1") (pin "1") (pinfunction "A_1") (pintype "passive"))
      (node (ref "S26_C1") (pin "2") (pinfunction "Ground_2") (pintype "power_in"))
      (node (ref "S26_D1") (pin "1") (pinfunction "A_1") (pintype "passive"))
      (node (ref "S27_C1") (pin "2") (pinfunction "Ground_2") (pintype "power_in"))
      (node (ref "S27_D1") (pin "1") (pinfunction "A_1") (pintype "passive"))
      (node (ref "S28_C1") (pin "2") (pinfunction "Ground_2") (pintype "power_in"))
      (node (ref "S28_D1") (pin "1") (pinfunction "A_1") (pintype "passive"))
      (node (ref "S29_C1") (pin "2") (pinfunction "Ground_2") (pintype "power_in"))
      (node (ref "S29_D1") (pin "1") (pinfunction "A_1") (pintype "passive"))
      (node (ref "S2_C1") (pin "2") (pinfunction "Ground_2") (pintype "power_in"))
      (node (ref "S2_D1") (pin "1") (pinfunction "A_1") (pintype "passive"))
      (node (ref "S30_C1") (pin "2") (pinfunction "Ground_2") (pintype "power_in"))
      (node (ref "S30_D1") (pin "1") (pinfunction "A_1") (pintype "passive"))
      (node (ref "S31_C1") (pin "2") (pinfunction "Ground_2") (pintype "power_in"))
      (node (ref "S31_D1") (pin "1") (pinfunction "A_1") (pintype "passive"))
      (node (ref "S32_C1") (pin "2") (pinfunction "Ground_2") (pintype "power_in"))
      (node (ref "S32_D1") (pin "1") (pinfunction "A_1") (pintype "passive"))
      (node (ref "S3_C1") (pin "2") (pinfunction "Ground_2") (pintype "power_in"))
      (node (ref "S3_D1") (pin "1") (pinfunction "A_1") (pintype "passive"))
      (node (ref "S4_C1") (pin "2") (pinfunction "Ground_2") (pintype "power_in"))
      (node (ref "S4_D1") (pin "1") (pinfunction "A_1") (pintype "passive"))
      (node (ref "S5_C1") (pin "2") (pinfunction "Ground_2") (pintype "power_in"))
      (node (ref "S5_D1") (pin "1") (pinfunction "A_1") (pintype "passive"))
      (node (ref "S6_C1") (pin "2") (pinfunction "Ground_2") (pintype "power_in"))
      (node (ref "S6_D1") (pin "1") (pinfunction "A_1") (pintype "passive"))
      (node (ref "S7_C1") (pin "2") (pinfunction "Ground_2") (pintype "power_in"))
      (node (ref "S7_D1") (pin "1") (pinfunction "A_1") (pintype "passive"))
      (node (ref "S8_C1") (pin "2") (pinfunction "Ground_2") (pintype "power_in"))
      (node (ref "S8_D1") (pin "1") (pinfunction "A_1") (pintype "passive"))
      (node (ref "S9_C1") (pin "2") (pinfunction "Ground_2") (pintype "power_in"))
      (node (ref "S9_D1") (pin "1") (pinfunction "A_1") (pintype "passive"))
    )
    (net (code "2") (name "/POWER") (class "Default")
      (node (ref "P1") (pin "1") (pinfunction "1_1") (pintype "passive"))
      (node (ref "S10_D3") (pin "2") (pinfunction "K_2") (pintype "passive"))
      (node (ref "S11_D3") (pin "2") (pinfunction "K_2") (pintype "passive"))
      (node (ref "S12_D3") (pin "2") (pinfunction "K_2") (pintype "passive"))
      (node (ref "S13_D3") (pin "2") (pinfunction "K_2") (pintype "passive"))
      (node (ref "S14_D3") (pin "2") (pinfunction "K_2") (pintype "passive"))
      (node (ref "S15_D3") (pin "2") (pinfunction "K_2") (pintype "passive"))
      (node (ref "S16_D3") (pin "2") (pinfunction "K_2") (pintype "passive"))
      (node (ref "S17_D3") (pin "2") (pinfunction "K_2") (pintype "passive"))
      (node (ref "S18_D3") (pin "2") (pinfunction "K_2") (pintype "passive"))
      (node (ref "S19_D3") (pin "2") (pinfunction "K_2") (pintype "passive"))
      (node (ref "S1_D3") (pin "2") (pinfunction "K_2") (pintype "passive"))
      (node (ref "S20_D3") (pin "2") (pinfunction "K_2") (pintype "passive"))
      (node (ref "S21_D3") (pin "2") (pinfunction "K_2") (pintype "passive"))
      (node (ref "S22_D3") (pin "2") (pinfunction "K_2") (pintype "passive"))
      (node (ref "S23_D3") (pin "2") (pinfunction "K_2") (pintype "passive"))
      (node (ref "S24_D3") (pin "2") (pinfunction "K_2") (pintype "passive"))
      (node (ref "S25_D3") (pin "2") (pinfunction "K_2") (pintype "passive"))
      (node (ref "S26_D3") (pin "2") (pinfunction "K_2") (pintype "passive"))
      (node (ref "S27_D3") (pin "2") (pinfunction "K_2") (pintype "passive"))
      (node (ref "S28_D3") (pin "2") (pinfunction "K_2") (pintype "passive"))
      (node (ref "S29_D3") (pin "2") (pinfunction "K_2") (pintype "passive"))
      (node (ref "S2_D3") (pin "2") (pinfunction "K_2") (pintype "passive"))
      (node (ref "S30_D3") (pin "2") (pinfunction "K_2") (pintype "passive"))
      (node (ref "S31_D3") (pin "2") (pinfunction "K_2") (pintype "passive"))
      (node (ref "S32_D3") (pin "2") (pinfunction "K_2") (pintype "passive"))
      (node (ref "S3_D3") (pin "2") (pinfunction "K_2") (pintype "passive"))
      (node (ref "S4_D3") (pin "2") (pinfunction "K_2") (pintype "passive"))
      (node (ref "S5_D3") (pin "2") (pinfunction "K_2") (pintype "passive"))
      (node (ref "S6_D3") (pin "2") (pinfunction "K_2") (pintype "passive"))
      (node (ref "S7_D3") (pin "2") (pinfunction "K_2") (pintype "passive"))
      (node (ref "S8_D3") (pin "2") (pinfunction "K_2") (pintype "passive"))
      (node (ref "S9_D3") (pin "2") (pinfunction "K_2") (pintype "passive"))
    )
    (net (code "3") (name "Net-(S1_C1-Positive)") (class "Default")
      (node (ref "S1_C1") (pin "1") (pinfunction "Positive_1") (pintype "power_in"))
      (node (ref "S1_C2") (pin "2") (pinfunction "Ground_2") (pintype "power_in"))
      (node (ref "S1_D1") (pin "2") (pinfunction "K_2") (pintype "passive"))
      (node (ref "S1_D2") (pin "1") (pinfunction "A_1") (pintype "passive"))
    )
    (net (code "4") (name "Net-(S1_C2-Positive)") (class "Default")
      (node (ref "S1_C2") (pin "1") (pinfunction "Positive_1") (pintype "power_in"))
      (node (ref "S1_D2") (pin "2") (pinfunction "K_2") (pintype "passive"))
      (node (ref "S1_D3") (pin "1") (pinfunction "A_1") (pintype "passive"))
    )
    (net (code "5") (name "Net-(S2_C1-Positive)") (class "Default")
      (node (ref "S2_C1") (pin "1") (pinfunction "Positive_1") (pintype "power_in"))
      (node (ref "S2_C2") (pin "2") (pinfunction "Ground_2") (pintype "power_in"))
      (node (ref "S2_D1") (pin "2") (pinfunction "K_2") (pintype "passive"))
      (node (ref "S2_D2") (pin "1") (pinfunction "A_1") (pintype "passive"))
    )
    (net (code "6") (name "Net-(S2_C2-Positive)") (class "Default")
      (node (ref "S2_C2") (pin "1") (pinfunction "Positive_1") (pintype "power_in"))
      (node (ref "S2_D2") (pin "2") (pinfunction "K_2") (pintype "passive"))
      (node (ref "S2_D3") (pin "1") (pinfunction "A_1") (pintype "passive"))
    )
    (net (code "7") (name "Net-(S3_C1-Positive)") (class "Default")
      (node (ref "S3_C1") (pin "1") (pinfunction "Positive_1") (pintype "power_in"))
      (node (ref "S3_C2") (pin "2") (pinfunction "Ground_2") (pintype "power_in"))
      (node (ref "S3_D1") (pin "2") (pinfunction "K_2") (pintype "passive"))
      (node (ref "S3_D2") (pin "1") (pinfunction "A_1") (pintype "passive"))
    )
    (net (code "8") (name "Net-(S3_C2-Positive)") (class "Default")
      (node (ref "S3_C2") (pin "1") (pinfunction "Positive_1") (pintype "power_in"))
      (node (ref "S3_D2") (pin "2") (pinfunction "K_2") (pintype "passive"))
      (node (ref "S3_D3") (pin "1") (pinfunction "A_1") (pintype "passive"))
    )
    (net (code "9") (name "Net-(S4_C1-Positive)") (class "Default")
      (node (ref "S4_C1") (pin "1") (pinfunction "Positive_1") (pintype "power_in"))
      (node (ref "S4_C2") (pin "2") (pinfunction "Ground_2") (pintype "power_in"))
      (node (ref "S4_D1") (pin "2") (pinfunction "K_2") (pintype "passive"))
      (node (ref "S4_D2") (pin "1") (pinfunction "A_1") (pintype "passive"))
    )
    (net (code "10") (name "Net-(S4_C2-Positive)") (class "Default")
      (node (ref "S4_C2") (pin "1") (pinfunction "Positive_1") (pintype "power_in"))
      (node (ref "S4_D2") (pin "2") (pinfunction "K_2") (pintype "passive"))
      (node (ref "S4_D3") (pin "1") (pinfunction "A_1") (pintype "passive"))
    )
    (net (code "11") (name "Net-(S5_C1-Positive)") (class "Default")
      (node (ref "S5_C1") (pin "1") (pinfunction "Positive_1") (pintype "power_in"))
      (node (ref "S5_C2") (pin "2") (pinfunction "Ground_2") (pintype "power_in"))
      (node (ref "S5_D1") (pin "2") (pinfunction "K_2") (pintype "passive"))
      (node (ref "S5_D2") (pin "1") (pinfunction "A_1") (pintype "passive"))
    )
    (net (code "12") (name "Net-(S5_C2-Positive)") (class "Default")
      (node (ref "S5_C2") (pin "1") (pinfunction "Positive_1") (pintype "power_in"))
      (node (ref "S5_D2") (pin "2") (pinfunction "K_2") (pintype "passive"))
      (node (ref "S5_D3") (pin "1") (pinfunction "A_1") (pintype "passive"))
    )
    (net (code "13") (name "Net-(S6_C1-Positive)") (class "Default")
      (node (ref "S6_C1") (pin "1") (pinfunction "Positive_1") (pintype "power_in"))
      (node (ref "S6_C2") (pin "2") (pinfunction "Ground_2") (pintype "power_in"))
      (node (ref "S6_D1") (pin "2") (pinfunction "K_2") (pintype "passive"))
      (node (ref "S6_D2") (pin "1") (pinfunction "A_1") (pintype "passive"))
    )
    (net (code "14") (name "Net-(S6_C2-Positive)") (class "Default")
      (node (ref "S6_C2") (pin "1") (pinfunction "Positive_1") (pintype "power_in"))
      (node (ref "S6_D2") (pin "2") (pinfunction "K_2") (pintype "passive"))
      (node (ref "S6_D3") (pin "1") (pinfunction "A_1") (pintype "passive"))
    )
    (net (code "15") (name "Net-(S7_C1-Positive)") (class "Default")
      (node (ref "S7_C1") (pin "1") (pinfunction "Positive_1") (pintype "power_in"))
      (node (ref "S7_C2") (pin "2") (pinfunction "Ground_2") (pintype "power_in"))
      (node (ref "S7_D1") (pin "2") (pinfunction "K_2") (pintype "passive"))
      (node (ref "S7_D2") (pin "1") (pinfunction "A_1") (pintype "passive"))
    )
    (net (code "16") (name "Net-(S7_C2-Positive)") (class "Default")
      (node (ref "S7_C2") (pin "1") (pinfunction "Positive_1") (pintype "power_in"))
      (node (ref "S7_D2") (pin "2") (pinfunction "K_2") (pintype "passive"))
      (node (ref "S7_D3") (pin "1") (pinfunction "A_1") (pintype "passive"))
    )
    (net (code "17") (name "Net-(S8_C1-Positive)") (class "Default")
      (node (ref "S8_C1") (pin "1") (pinfunction "Positive_1") (pintype "power_in"))
      (node (ref "S8_C2") (pin "2") (pinfunction "Ground_2") (pintype "power_in"))
      (node (ref "S8_D1") (pin "2") (pinfunction "K_2") (pintype "passive"))
      (node (ref "S8_D2") (pin "1") (pinfunction "A_1") (pintype "passive"))
    )
    (net (code "18") (name "Net-(S8_C2-Positive)") (class "Default")
      (node (ref "S8_C2") (pin "1") (pinfunction "Positive_1") (pintype "power_in"))
      (node (ref "S8_D2") (pin "2") (pinfunction "K_2") (pintype "passive"))
      (node (ref "S8_D3") (pin "1") (pinfunction "A_1") (pintype "passive"))
    )
    (net (code "19") (name "Net-(S9_C1-Positive)") (class "Default")
      (node (ref "S9_C1") (pin "1") (pinfunction "Positive_1") (pintype "power_in"))
      (node (ref "S9_C2") (pin "2") (pinfunction "Ground_2") (pintype "power_in"))
      (node (ref "S9_D1") (pin "2") (pinfunction "K_2") (pintype "passive"))
      (node (ref "S9_D2") (pin "1") (pinfunction "A_1") (pintype "passive"))
    )
    (net (code "20") (name "Net-(S9_C2-Positive)") (class "Default")
      (node (ref "S9_C2") (pin "1") (pinfunction "Positive_1") (pintype "power_in"))
      (node (ref "S9_D2") (pin "2") (pinfunction "K_2") (pintype "passive"))
      (node (ref "S9_D3") (pin "1") (pinfunction "A_1") (pintype "passive"))
    )
    (net (code "21") (name "Net-(S10_C1-Positive)") (class "Default")
      (node (ref "S10_C1") (pin "1") (pinfunction "Positive_1") (pintype "power_in"))
      (node (ref "S10_C2") (pin "2") (pinfunction "Ground_2") (pintype "power_in"))
      (node (ref "S10_D1") (pin "2") (pinfunction "K_2") (pintype "passive"))
      (node (ref "S10_D2") (pin "1") (pinfunction "A_1") (pintype "passive"))
    )
    (net (code "22") (name "Net-(S10_C2-Positive)") (class "Default")
      (node (ref "S10_C2") (pin "1") (pinfunction "Positive_1") (pintype "power_in"))
      (node (ref "S10_D2") (pin "2") (pinfunction "K_2") (pintype "passive"))
      (node (ref "S10_D3") (pin "1") (pinfunction "A_1") (pintype "passive"))
    )
    (net (code "23") (name "Net-(S11_C1-Positive)") (class "Default")
      (node (ref "S11_C1") (pin "1") (pinfunction "Positive_1") (pintype "power_in"))
      (node (ref "S11_C2") (pin "2") (pinfunction "Ground_2") (pintype "power_in"))
      (node (ref "S11_D1") (pin "2") (pinfunction "K_2") (pintype "passive"))
      (node (ref "S11_D2") (pin "1") (pinfunction "A_1") (pintype "passive"))
    )
    (net (code "24") (name "Net-(S11_C2-Positive)") (class "Default")
      (node (ref "S11_C2") (pin "1") (pinfunction "Positive_1") (pintype "power_in"))
      (node (ref "S11_D2") (pin "2") (pinfunction "K_2") (pintype "passive"))
      (node (ref "S11_D3") (pin "1") (pinfunction "A_1") (pintype "passive"))
    )
    (net (code "25") (name "Net-(S12_C1-Positive)") (class "Default")
      (node (ref "S12_C1") (pin "1") (pinfunction "Positive_1") (pintype "power_in"))
      (node (ref "S12_C2") (pin "2") (pinfunction "Ground_2") (pintype "power_in"))
      (node (ref "S12_D1") (pin "2") (pinfunction "K_2") (pintype "passive"))
      (node (ref "S12_D2") (pin "1") (pinfunction "A_1") (pintype "passive"))
    )
    (net (code "26") (name "Net-(S12_C2-Positive)") (class "Default")
      (node (ref "S12_C2") (pin "1") (pinfunction "Positive_1") (pintype "power_in"))
      (node (ref "S12_D2") (pin "2") (pinfunction "K_2") (pintype "passive"))
      (node (ref "S12_D3") (pin "1") (pinfunction "A_1") (pintype "passive"))
    )
    (net (code "27") (name "Net-(S13_C1-Positive)") (class "Default")
      (node (ref "S13_C1") (pin "1") (pinfunction "Positive_1") (pintype "power_in"))
      (node (ref "S13_C2") (pin "2") (pinfunction "Ground_2") (pintype "power_in"))
      (node (ref "S13_D1") (pin "2") (pinfunction "K_2") (pintype "passive"))
      (node (ref "S13_D2") (pin "1") (pinfunction "A_1") (pintype "passive"))
    )
    (net (code "28") (name "Net-(S13_C2-Positive)") (class "Default")
      (node (ref "S13_C2") (pin "1") (pinfunction "Positive_1") (pintype "power_in"))
      (node (ref "S13_D2") (pin "2") (pinfunction "K_2") (pintype "passive"))
      (node (ref "S13_D3") (pin "1") (pinfunction "A_1") (pintype "passive"))
    )
    (net (code "29") (name "Net-(S14_C1-Positive)") (class "Default")
      (node (ref "S14_C1") (pin "1") (pinfunction "Positive_1") (pintype "power_in"))
      (node (ref "S14_C2") (pin "2") (pinfunction "Ground_2") (pintype "power_in"))
      (node (ref "S14_D1") (pin "2") (pinfunction "K_2") (pintype "passive"))
      (node (ref "S14_D2") (pin "1") (pinfunction "A_1") (pintype "passive"))
    )
    (net (code "30") (name "Net-(S14_C2-Positive)") (class "Default")
      (node (ref "S14_C2") (pin "1") (pinfunction "Positive_1") (pintype "power_in"))
      (node (ref "S14_D2") (pin "2") (pinfunction "K_2") (pintype "passive"))
      (node (ref "S14_D3") (pin "1") (pinfunction "A_1") (pintype "passive"))
    )
    (net (code "31") (name "Net-(S15_C1-Positive)") (class "Default")
      (node (ref "S15_C1") (pin "1") (pinfunction "Positive_1") (pintype "power_in"))
      (node (ref "S15_C2") (pin "2") (pinfunction "Ground_2") (pintype "power_in"))
      (node (ref "S15_D1") (pin "2") (pinfunction "K_2") (pintype "passive"))
      (node (ref "S15_D2") (pin "1") (pinfunction "A_1") (pintype "passive"))
    )
    (net (code "32") (name "Net-(S15_C2-Positive)") (class "Default")
      (node (ref "S15_C2") (pin "1") (pinfunction "Positive_1") (pintype "power_in"))
      (node (ref "S15_D2") (pin "2") (pinfunction "K_2") (pintype "passive"))
      (node (ref "S15_D3") (pin "1") (pinfunction "A_1") (pintype "passive"))
    )
    (net (code "33") (name "Net-(S16_C1-Positive)") (class "Default")
      (node (ref "S16_C1") (pin "1") (pinfunction "Positive_1") (pintype "power_in"))
      (node (ref "S16_C2") (pin "2") (pinfunction "Ground_2") (pintype "power_in"))
      (node (ref "S16_D1") (pin "2") (pinfunction "K_2") (pintype "passive"))
      (node (ref "S16_D2") (pin "1") (pinfunction "A_1") (pintype "passive"))
    )
    (net (code "34") (name "Net-(S16_C2-Positive)") (class "Default")
      (node (ref "S16_C2") (pin "1") (pinfunction "Positive_1") (pintype "power_in"))
      (node (ref "S16_D2") (pin "2") (pinfunction "K_2") (pintype "passive"))
      (node (ref "S16_D3") (pin "1") (pinfunction "A_1") (pintype "passive"))
    )
    (net (code "35") (name "Net-(S17_C1-Positive)") (class "Default")
      (node (ref "S17_C1") (pin "1") (pinfunction "Positive_1") (pintype "power_in"))
      (node (ref "S17_C2") (pin "2") (pinfunction "Ground_2") (pintype "power_in"))
      (node (ref "S17_D1") (pin "2") (pinfunction "K_2") (pintype "passive"))
      (node (ref "S17_D2") (pin "1") (pinfunction "A_1") (pintype "passive"))
    )
    (net (code "36") (name "Net-(S17_C2-Positive)") (class "Default")
      (node (ref "S17_C2") (pin "1") (pinfunction "Positive_1") (pintype "power_in"))
      (node (ref "S17_D2") (pin "2") (pinfunction "K_2") (pintype "passive"))
      (node (ref "S17_D3") (pin "1") (pinfunction "A_1") (pintype "passive"))
    )
    (net (code "37") (name "Net-(S18_C1-Positive)") (class "Default")
      (node (ref "S18_C1") (pin "1") (pinfunction "Positive_1") (pintype "power_in"))
      (node (ref "S18_C2") (pin "2") (pinfunction "Ground_2") (pintype "power_in"))
      (node (ref "S18_D1") (pin "2") (pinfunction "K_2") (pintype "passive"))
      (node (ref "S18_D2") (pin "1") (pinfunction "A_1") (pintype "passive"))
    )
    (net (code "38") (name "Net-(S18_C2-Positive)") (class "Default")
      (node (ref "S18_C2") (pin "1") (pinfunction "Positive_1") (pintype "power_in"))
      (node (ref "S18_D2") (pin "2") (pinfunction "K_2") (pintype "passive"))
      (node (ref "S18_D3") (pin "1") (pinfunction "A_1") (pintype "passive"))
    )
    (net (code "39") (name "Net-(S19_C1-Positive)") (class "Default")
      (node (ref "S19_C1") (pin "1") (pinfunction "Positive_1") (pintype "power_in"))
      (node (ref "S19_C2") (pin "2") (pinfunction "Ground_2") (pintype "power_in"))
      (node (ref "S19_D1") (pin "2") (pinfunction "K_2") (pintype "passive"))
      (node (ref "S19_D2") (pin "1") (pinfunction "A_1") (pintype "passive"))
    )
    (net (code "40") (name "Net-(S19_C2-Positive)") (class "Default")
      (node (ref "S19_C2") (pin "1") (pinfunction "Positive_1") (pintype "power_in"))
      (node (ref "S19_D2") (pin "2") (pinfunction "K_2") (pintype "passive"))
      (node (ref "S19_D3") (pin "1") (pinfunction "A_1") (pintype "passive"))
    )
    (net (code "41") (name "Net-(S20_C1-Positive)") (class "Default")
      (node (ref "S20_C1") (pin "1") (pinfunction "Positive_1") (pintype "power_in"))
      (node (ref "S20_C2") (pin "2") (pinfunction "Ground_2") (pintype "power_in"))
      (node (ref "S20_D1") (pin "2") (pinfunction "K_2") (pintype "passive"))
      (node (ref "S20_D2") (pin "1") (pinfunction "A_1") (pintype "passive"))
    )
    (net (code "42") (name "Net-(S20_C2-Positive)") (class "Default")
      (node (ref "S20_C2") (pin "1") (pinfunction "Positive_1") (pintype "power_in"))
      (node (ref "S20_D2") (pin "2") (pinfunction "K_2") (pintype "passive"))
      (node (ref "S20_D3") (pin "1") (pinfunction "A_1") (pintype "passive"))
    )
    (net (code "43") (name "Net-(S21_C1-Positive)") (class "Default")
      (node (ref "S21_C1") (pin "1") (pinfunction "Positive_1") (pintype "power_in"))
      (node (ref "S21_C2") (pin "2") (pinfunction "Ground_2") (pintype "power_in"))
      (node (ref "S21_D1") (pin "2") (pinfunction "K_2") (pintype "passive"))
      (node (ref "S21_D2") (pin "1") (pinfunction "A_1") (pintype "passive"))
    )
    (net (code "44") (name "Net-(S21_C2-Positive)") (class "Default")
      (node (ref "S21_C2") (pin "1") (pinfunction "Positive_1") (pintype "power_in"))
      (node (ref "S21_D2") (pin "2") (pinfunction "K_2") (pintype "passive"))
      (node (ref "S21_D3") (pin "1") (pinfunction "A_1") (pintype "passive"))
    )
    (net (code "45") (name "Net-(S22_C1-Positive)") (class "Default")
      (node (ref "S22_C1") (pin "1") (pinfunction "Positive_1") (pintype "power_in"))
      (node (ref "S22_C2") (pin "2") (pinfunction "Ground_2") (pintype "power_in"))
      (node (ref "S22_D1") (pin "2") (pinfunction "K_2") (pintype "passive"))
      (node (ref "S22_D2") (pin "1") (pinfunction "A_1") (pintype "passive"))
    )
    (net (code "46") (name "Net-(S22_C2-Positive)") (class "Default")
      (node (ref "S22_C2") (pin "1") (pinfunction "Positive_1") (pintype "power_in"))
      (node (ref "S22_D2") (pin "2") (pinfunction "K_2") (pintype "passive"))
      (node (ref "S22_D3") (pin "1") (pinfunction "A_1") (pintype "passive"))
    )
    (net (code "47") (name "Net-(S23_C1-Positive)") (class "Default")
      (node (ref "S23_C1") (pin "1") (pinfunction "Positive_1") (pintype "power_in"))
      (node (ref "S23_C2") (pin "2") (pinfunction "Ground_2") (pintype "power_in"))
      (node (ref "S23_D1") (pin "2") (pinfunction "K_2") (pintype "passive"))
      (node (ref "S23_D2") (pin "1") (pinfunction "A_1") (pintype "passive"))
    )
    (net (code "48") (name "Net-(S23_C2-Positive)") (class "Default")
      (node (ref "S23_C2") (pin "1") (pinfunction "Positive_1") (pintype "power_in"))
      (node (ref "S23_D2") (pin "2") (pinfunction "K_2") (pintype "passive"))
      (node (ref "S23_D3") (pin "1") (pinfunction "A_1") (pintype "passive"))
    )
    (net (code "49") (name "Net-(S24_C1-Positive)") (class "Default")
      (node (ref "S24_C1") (pin "1") (pinfunction "Positive_1") (pintype "power_in"))
      (node (ref "S24_C2") (pin "2") (pinfunction "Ground_2") (pintype "power_in"))
      (node (ref "S24_D1") (pin "2") (pinfunction "K_2") (pintype "passive"))
      (node (ref "S24_D2") (pin "1") (pinfunction "A_1") (pintype "passive"))
    )
    (net (code "50") (name "Net-(S24_C2-Positive)") (class "Default")
      (node (ref "S24_C2") (pin "1") (pinfunction "Positive_1") (pintype "power_in"))
      (node (ref "S24_D2") (pin "2") (pinfunction "K_2") (pintype "passive"))
      (node (ref "S24_D3") (pin "1") (pinfunction "A_1") (pintype "passive"))
    )
    (net (code "51") (name "Net-(S25_C1-Positive)") (class "Default")
      (node (ref "S25_C1") (pin "1") (pinfunction "Positive_1") (pintype "power_in"))
      (node (ref "S25_C2") (pin "2") (pinfunction "Ground_2") (pintype "power_in"))
      (node (ref "S25_D1") (pin "2") (pinfunction "K_2") (pintype "passive"))
      (node (ref "S25_D2") (pin "1") (pinfunction "A_1") (pintype "passive"))
    )
    (net (code "52") (name "Net-(S25_C2-Positive)") (class "Default")
      (node (ref "S25_C2") (pin "1") (pinfunction "Positive_1") (pintype "power_in"))
      (node (ref "S25_D2") (pin "2") (pinfunction "K_2") (pintype "passive"))
      (node (ref "S25_D3") (pin "1") (pinfunction "A_1") (pintype "passive"))
    )
    (net (code "53") (name "Net-(S26_C1-Positive)") (class "Default")
      (node (ref "S26_C1") (pin "1") (pinfunction "Positive_1") (pintype "power_in"))
      (node (ref "S26_C2") (pin "2") (pinfunction "Ground_2") (pintype "power_in"))
      (node (ref "S26_D1") (pin "2") (pinfunction "K_2") (pintype "passive"))
      (node (ref "S26_D2") (pin "1") (pinfunction "A_1") (pintype "passive"))
    )
    (net (code "54") (name "Net-(S26_C2-Positive)") (class "Default")
      (node (ref "S26_C2") (pin "1") (pinfunction "Positive_1") (pintype "power_in"))
      (node (ref "S26_D2") (pin "2") (pinfunction "K_2") (pintype "passive"))
      (node (ref "S26_D3") (pin "1") (pinfunction "A_1") (pintype "passive"))
    )
    (net (code "55") (name "Net-(S27_C1-Positive)") (class "Default")
      (node (ref "S27_C1") (pin "1") (pinfunction "Positive_1") (pintype "power_in"))
      (node (ref "S27_C2") (pin "2") (pinfunction "Ground_2") (pintype "power_in"))
      (node (ref "S27_D1") (pin "2") (pinfunction "K_2") (pintype "passive"))
      (node (ref "S27_D2") (pin "1") (pinfunction "A_1") (pintype "passive"))
    )
    (net (code "56") (name "Net-(S27_C2-Positive)") (class "Default")
      (node (ref "S27_C2") (pin "1") (pinfunction "Positive_1") (pintype "power_in"))
      (node (ref "S27_D2") (pin "2") (pinfunction "K_2") (pintype "passive"))
      (node (ref "S27_D3") (pin "1") (pinfunction "A_1") (pintype "passive"))
    )
    (net (code "57") (name "Net-(S28_C1-Positive)") (class "Default")
      (node (ref "S28_C1") (pin "1") (pinfunction "Positive_1") (pintype "power_in"))
      (node (ref "S28_C2") (pin "2") (pinfunction "Ground_2") (pintype "power_in"))
      (node (ref "S28_D1") (pin "2") (pinfunction "K_2") (pintype "passive"))
      (node (ref "S28_D2") (pin "1") (pinfunction "A_1") (pintype "passive"))
    )
    (net (code "58") (name "Net-(S28_C2-Positive)") (class "Default")
      (node (ref "S28_C2") (pin "1") (pinfunction "Positive_1") (pintype "power_in"))
      (node (ref "S28_D2") (pin "2") (pinfunction "K_2") (pintype "passive"))
      (node (ref "S28_D3") (pin "1") (pinfunction "A_1") (pintype "passive"))
    )
    (net (code "59") (name "Net-(S29_C1-Positive)") (class "Default")
      (node (ref "S29_C1") (pin "1") (pinfunction "Positive_1") (pintype "power_in"))
      (node (ref "S29_C2") (pin "2") (pinfunction "Ground_2") (pintype "power_in"))
      (node (ref "S29_D1") (pin "2") (pinfunction "K_2") (pintype "passive"))
      (node (ref "S29_D2") (pin "1") (pinfunction "A_1") (pintype "passive"))
    )
    (net (code "60") (name "Net-(S29_C2-Positive)") (class "Default")
      (node (ref "S29_C2") (pin "1") (pinfunction "Positive_1") (pintype "power_in"))
      (node (ref "S29_D2") (pin "2") (pinfunction "K_2") (pintype "passive"))
      (node (ref "S29_D3") (pin "1") (pinfunction "A_1") (pintype "passive"))
    )
    (net (code "61") (name "Net-(S30_C1-Positive)") (class "Default")
      (node (ref "S30_C1") (pin "1") (pinfunction "Positive_1") (pintype "power_in"))
      (node (ref "S30_C2") (pin "2") (pinfunction "Ground_2") (pintype "power_in"))
      (node (ref "S30_D1") (pin "2") (pinfunction "K_2") (pintype "passive"))
      (node (ref "S30_D2") (pin "1") (pinfunction "A_1") (pintype "passive"))
    )
    (net (code "62") (name "Net-(S30_C2-Positive)") (class "Default")
      (node (ref "S30_C2") (pin "1") (pinfunction "Positive_1") (pintype "power_in"))
      (node (ref "S30_D2") (pin "2") (pinfunction "K_2") (pintype "passive"))
      (node (ref "S30_D3") (pin "1") (pinfunction "A_1") (pintype "passive"))
    )
    (net (code "63") (name "Net-(S31_C1-Positive)") (class "Default")
      (node (ref "S31_C1") (pin "1") (pinfunction "Positive_1") (pintype "power_in"))
      (node (ref "S31_C2") (pin "2") (pinfunction "Ground_2") (pintype "power_in"))
      (node (ref "S31_D1") (pin "2") (pinfunction "K_2") (pintype "passive"))
      (node (ref "S31_D2") (pin "1") (pinfunction "A_1") (pintype "passive"))
    )
    (net (code "64") (name "Net-(S31_C2-Positive)") (class "Default")
      (node (ref "S31_C2") (pin "1") (pinfunction "Positive_1") (pintype "power_in"))
      (node (ref "S31_D2") (pin "2") (pinfunction "K_2") (pintype "passive"))
      (node (ref "S31_D3") (pin "1") (pinfunction "A_1") (pintype "passive"))
    )
    (net (code "65") (name "Net-(S32_C1-Positive)") (class "Default")
      (node (ref "S32_C1") (pin "1") (pinfunction "Positive_1") (pintype "power_in"))
      (node (ref "S32_C2") (pin "2") (pinfunction "Ground_2") (pintype "power_in"))
      (node (ref "S32_D1") (pin "2") (pinfunction "K_2") (pintype "passive"))
      (node (ref "S32_D2") (pin "1") (pinfunction "A_1") (pintype "passive"))
    )
    (net (code "66") (name "Net-(S32_C2-Positive)") (class "Default")
      (node (ref "S32_C2") (pin "1") (pinfunction "Positive_1") (pintype "power_in"))
      (node (ref "S32_D2") (pin "2") (pinfunction "K_2") (pintype "passive"))
      (node (ref "S32_D3") (pin "1") (pinfunction "A_1") (pintype "passive"))
    )
  )
)
